# 05_-_Connector.net
KiCad netlist of a schematic drawn in Altium Designer
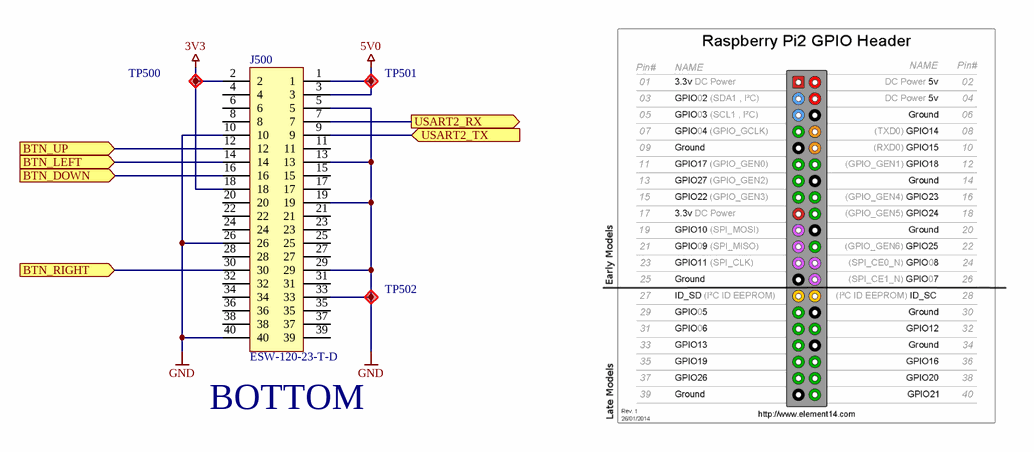
[diagram p0: 05 - Connector.SchDoc]

(export (version "E")
  (design (tool "Eeschema 10.0.6"))
  (components
    (comp (ref "J500")
      (value "ESW-120-23-T-D")
      (footprint "ESW-120-23-T-D-Footprint-1")
      (description "40 Position Elevated Socket Connector 0.100\" (2.54mm) Through Hole Tin")
      (fields (field (name "MANUFACTURER") "Samtec Inc."))
      (libsource (lib "Miromico AG") (part "ESW-120-23-T-D-Symbol-1"))
    )
    (comp (ref "TP500")
      (value "Testpoint")
      (footprint "Testpoint SMD 1.5mm")
      (description "Testpoint various footprints")
      (libsource (lib "Miromico AG") (part "Testpoint"))
    )
    (comp (ref "TP501")
      (value "Testpoint")
      (footprint "Testpoint SMD 1.5mm")
      (description "Testpoint various footprints")
      (libsource (lib "Miromico AG") (part "Testpoint"))
    )
    (comp (ref "TP502")
      (value "Testpoint")
      (footprint "Testpoint SMD 1.5mm")
      (description "Testpoint various footprints")
      (libsource (lib "Miromico AG") (part "Testpoint"))
    )
  )
  (nets
    (net (code "1") (name "/BTN_DOWN") (class "Default")
      (node (ref "J500") (pin "16") (pinfunction "16_16") (pintype "passive"))
    )
    (net (code "2") (name "/BTN_LEFT") (class "Default")
      (node (ref "J500") (pin "14") (pinfunction "14_14") (pintype "passive"))
    )
    (net (code "3") (name "/BTN_RIGHT") (class "Default")
      (node (ref "J500") (pin "30") (pinfunction "30_30") (pintype "passive"))
    )
    (net (code "4") (name "/BTN_UP") (class "Default")
      (node (ref "J500") (pin "12") (pinfunction "12_12") (pintype "passive"))
    )
    (net (code "5") (name "/USART2_RX") (class "Default")
      (node (ref "J500") (pin "7") (pinfunction "7_7") (pintype "passive"))
    )
    (net (code "6") (name "/USART2_TX") (class "Default")
      (node (ref "J500") (pin "9") (pinfunction "9_9") (pintype "passive"))
    )
    (net (code "7") (name "3V3") (class "Default")
      (node (ref "J500") (pin "18") (pinfunction "18_18") (pintype "passive"))
      (node (ref "J500") (pin "2") (pinfunction "2_2") (pintype "passive"))
      (node (ref "TP500") (pin "1") (pinfunction "1_1") (pintype "passive"))
    )
    (net (code "8") (name "5V0") (class "Default")
      (node (ref "J500") (pin "1") (pinfunction "1_1") (pintype "passive"))
      (node (ref "J500") (pin "3") (pinfunction "3_3") (pintype "passive"))
      (node (ref "TP501") (pin "1") (pinfunction "1_1") (pintype "passive"))
    )
    (net (code "9") (name "GND") (class "Default")
      (node (ref "J500") (pin "10") (pinfunction "10_10") (pintype "passive"))
      (node (ref "J500") (pin "13") (pinfunction "13_13") (pintype "passive"))
      (node (ref "J500") (pin "19") (pinfunction "19_19") (pintype "passive"))
      (node (ref "J500") (pin "26") (pinfunction "26_26") (pintype "passive"))
      (node (ref "J500") (pin "29") (pinfunction "29_29") (pintype "passive"))
      (node (ref "J500") (pin "33") (pinfunction "33_33") (pintype "passive"))
      (node (ref "J500") (pin "40") (pinfunction "40_40") (pintype "passive"))
      (node (ref "J500") (pin "5") (pinfunction "5_5") (pintype "passive"))
      (node (ref "TP502") (pin "1") (pinfunction "1_1") (pintype "passive"))
    )
    (net (code "10") (name "unconnected-(J500-Pad4)") (class "Default")
      (node (ref "J500") (pin "4") (pinfunction "4_4") (pintype "passive"))
    )
    (net (code "11") (name "unconnected-(J500-Pad6)") (class "Default")
      (node (ref "J500") (pin "6") (pinfunction "6_6") (pintype "passive"))
    )
    (net (code "12") (name "unconnected-(J500-Pad8)") (class "Default")
      (node (ref "J500") (pin "8") (pinfunction "8_8") (pintype "passive"))
    )
    (net (code "13") (name "unconnected-(J500-Pad11)") (class "Default")
      (node (ref "J500") (pin "11") (pinfunction "11_11") (pintype "passive"))
    )
    (net (code "14") (name "unconnected-(J500-Pad15)") (class "Default")
      (node (ref "J500") (pin "15") (pinfunction "15_15") (pintype "passive"))
    )
    (net (code "15") (name "unconnected-(J500-Pad17)") (class "Default")
      (node (ref "J500") (pin "17") (pinfunction "17_17") (pintype "passive"))
    )
    (net (code "16") (name "unconnected-(J500-Pad20)") (class "Default")
      (node (ref "J500") (pin "20") (pinfunction "20_20") (pintype "passive"))
    )
    (net (code "17") (name "unconnected-(J500-Pad21)") (class "Default")
      (node (ref "J500") (pin "21") (pinfunction "21_21") (pintype "passive"))
    )
    (net (code "18") (name "unconnected-(J500-Pad22)") (class "Default")
      (node (ref "J500") (pin "22") (pinfunction "22_22") (pintype "passive"))
    )
    (net (code "19") (name "unconnected-(J500-Pad23)") (class "Default")
      (node (ref "J500") (pin "23") (pinfunction "23_23") (pintype "passive"))
    )
    (net (code "20") (name "unconnected-(J500-Pad24)") (class "Default")
      (node (ref "J500") (pin "24") (pinfunction "24_24") (pintype "passive"))
    )
    (net (code "21") (name "unconnected-(J500-Pad25)") (class "Default")
      (node (ref "J500") (pin "25") (pinfunction "25_25") (pintype "passive"))
    )
    (net (code "22") (name "unconnected-(J500-Pad27)") (class "Default")
      (node (ref "J500") (pin "27") (pinfunction "27_27") (pintype "passive"))
    )
    (net (code "23") (name "unconnected-(J500-Pad28)") (class "Default")
      (node (ref "J500") (pin "28") (pinfunction "28_28") (pintype "passive"))
    )
    (net (code "24") (name "unconnected-(J500-Pad31)") (class "Default")
      (node (ref "J500") (pin "31") (pinfunction "31_31") (pintype "passive"))
    )
    (net (code "25") (name "unconnected-(J500-Pad32)") (class "Default")
      (node (ref "J500") (pin "32") (pinfunction "32_32") (pintype "passive"))
    )
    (net (code "26") (name "unconnected-(J500-Pad34)") (class "Default")
      (node (ref "J500") (pin "34") (pinfunction "34_34") (pintype "passive"))
    )
    (net (code "27") (name "unconnected-(J500-Pad35)") (class "Default")
      (node (ref "J500") (pin "35") (pinfunction "35_35") (pintype "passive"))
    )
    (net (code "28") (name "unconnected-(J500-Pad36)") (class "Default")
      (node (ref "J500") (pin "36") (pinfunction "36_36") (pintype "passive"))
    )
    (net (code "29") (name "unconnected-(J500-Pad37)") (class "Default")
      (node (ref "J500") (pin "37") (pinfunction "37_37") (pintype "passive"))
    )
    (net (code "30") (name "unconnected-(J500-Pad38)") (class "Default")
      (node (ref "J500") (pin "38") (pinfunction "38_38") (pintype "passive"))
    )
    (net (code "31") (name "unconnected-(J500-Pad39)") (class "Default")
      (node (ref "J500") (pin "39") (pinfunction "39_39") (pintype "passive"))
    )
  )
)
